# Board_Design.net
KiCad netlist of a schematic drawn in EAGLE
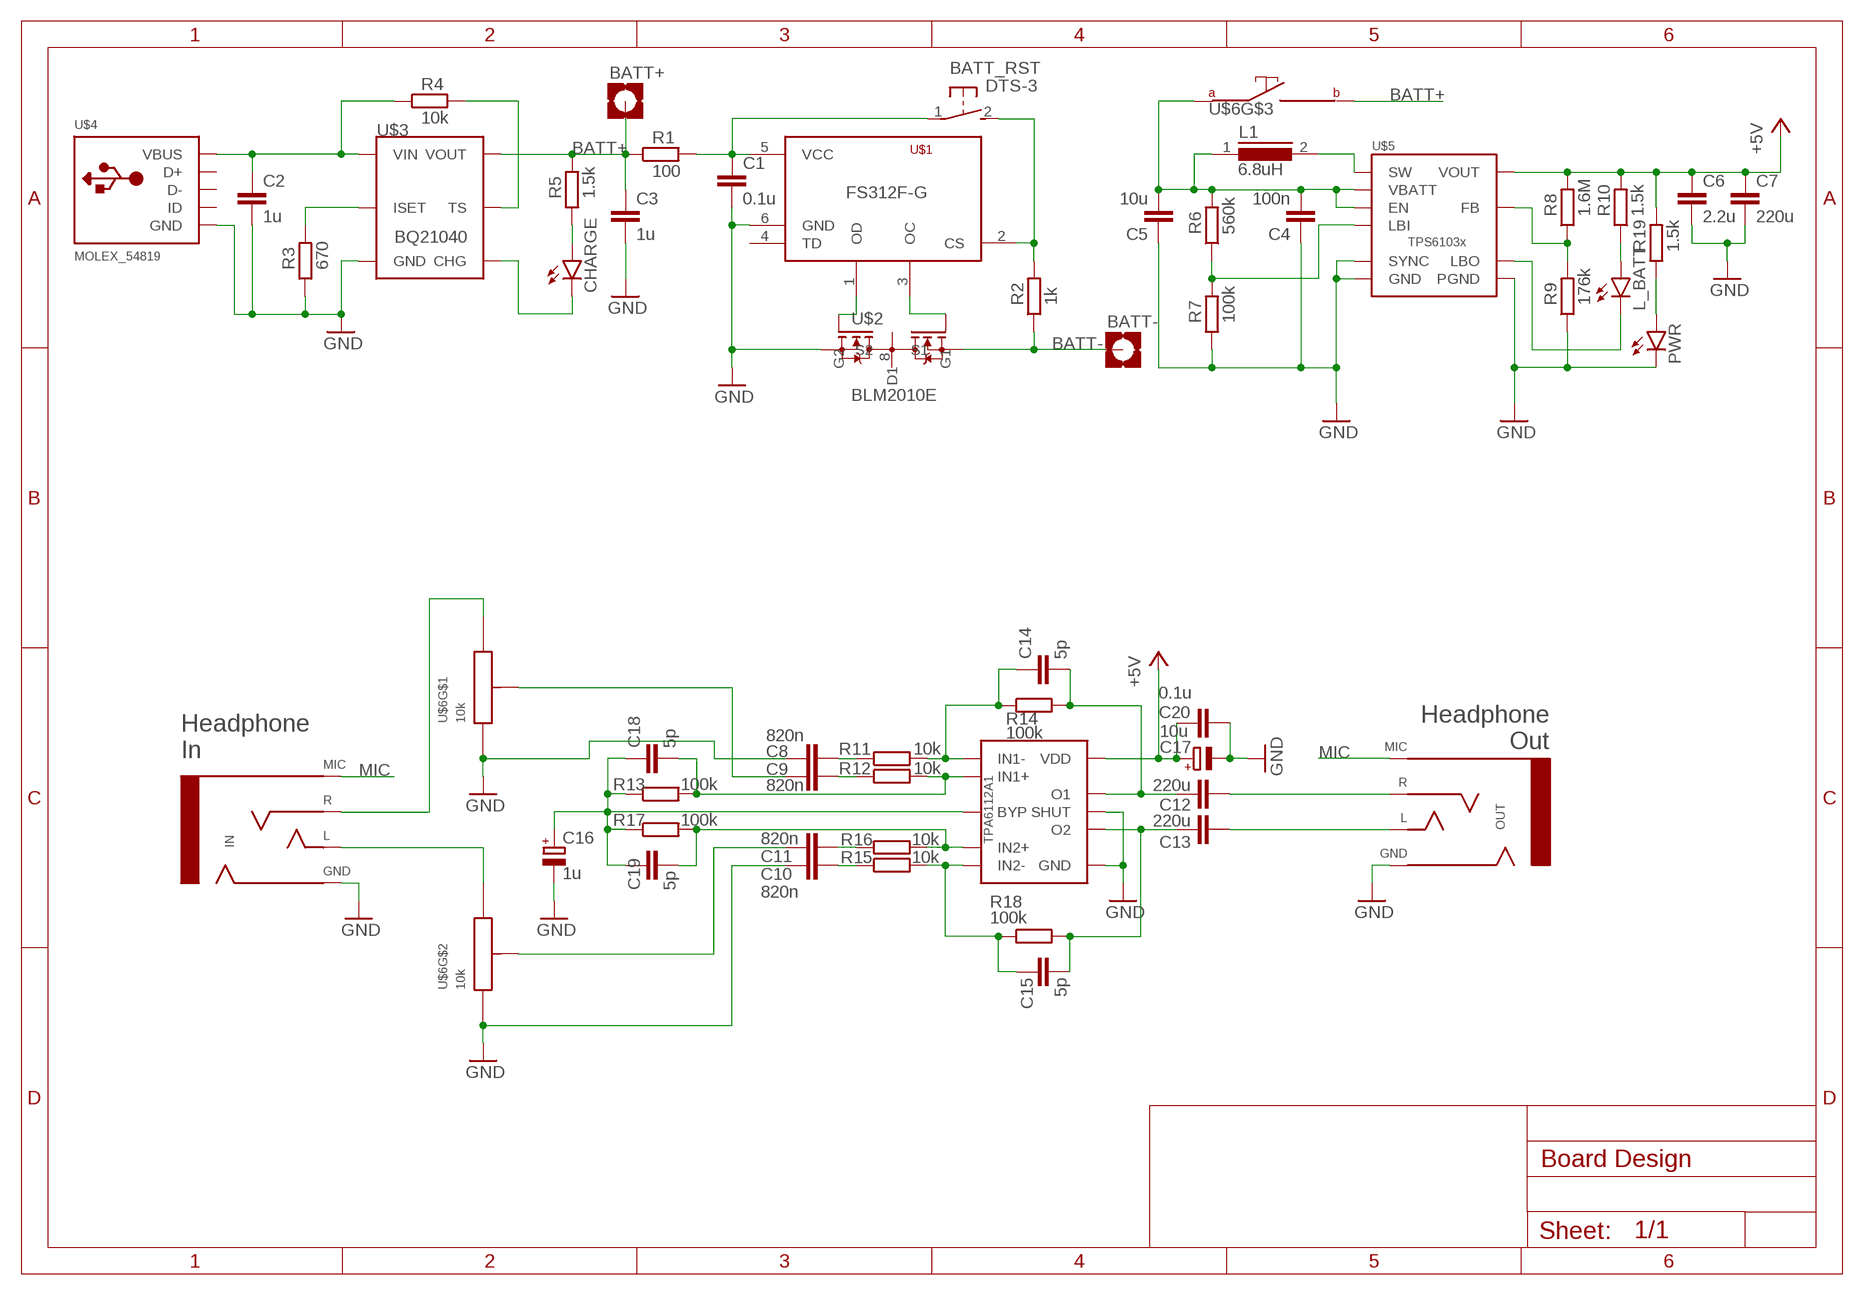
[diagram p0: schematic, sheet 1]

(export (version "E")
  (design (tool "Eeschema 10.0.6"))
  (components
    (comp (ref "BATT+")
      (value "MOUNT-PAD-SQUARE2.8")
      (footprint "eagle-import:2,8-PAD-SQUARE")
      (libsource (lib "eagle-import") (part "MOUNT-PAD-SQUARE2.8"))
    )
    (comp (ref "BATT-")
      (value "MOUNT-PAD-SQUARE2.8")
      (footprint "eagle-import:2,8-PAD-SQUARE")
      (libsource (lib "eagle-import") (part "MOUNT-PAD-SQUARE2.8"))
    )
    (comp (ref "BATT_RST")
      (value "DTS-3")
      (footprint "eagle-import:DTS-3")
      (libsource (lib "eagle-import") (part "DTS-3"))
    )
    (comp (ref "C1")
      (value "0.1u")
      (footprint "eagle-import:C1206")
      (libsource (lib "eagle-import") (part "C-EUC1206"))
    )
    (comp (ref "C2")
      (value "1u")
      (footprint "eagle-import:C1206")
      (libsource (lib "eagle-import") (part "C-EUC1206"))
    )
    (comp (ref "C3")
      (value "1u")
      (footprint "eagle-import:C1206")
      (libsource (lib "eagle-import") (part "C-EUC1206"))
    )
    (comp (ref "C4")
      (value "100n")
      (footprint "eagle-import:C1206")
      (libsource (lib "eagle-import") (part "C-EUC1206"))
    )
    (comp (ref "C5")
      (value "10u")
      (footprint "eagle-import:C1206")
      (libsource (lib "eagle-import") (part "C-EUC1206"))
    )
    (comp (ref "C6")
      (value "2.2u")
      (footprint "eagle-import:C1206")
      (libsource (lib "eagle-import") (part "C-EUC1206"))
    )
    (comp (ref "C7")
      (value "220u")
      (footprint "eagle-import:C1206")
      (libsource (lib "eagle-import") (part "C-EUC1206"))
    )
    (comp (ref "C8")
      (value "820n")
      (footprint "eagle-import:C1812")
      (libsource (lib "eagle-import") (part "C-EUC1812"))
    )
    (comp (ref "C9")
      (value "820n")
      (footprint "eagle-import:C1812")
      (libsource (lib "eagle-import") (part "C-EUC1812"))
    )
    (comp (ref "C10")
      (value "820n")
      (footprint "eagle-import:C1812")
      (libsource (lib "eagle-import") (part "C-EUC1812"))
    )
    (comp (ref "C11")
      (value "820n")
      (footprint "eagle-import:C1812")
      (libsource (lib "eagle-import") (part "C-EUC1812"))
    )
    (comp (ref "C12")
      (value "220u")
      (footprint "eagle-import:C1210")
      (libsource (lib "eagle-import") (part "C-EUC1210"))
    )
    (comp (ref "C13")
      (value "220u")
      (footprint "eagle-import:C1210")
      (libsource (lib "eagle-import") (part "C-EUC1210"))
    )
    (comp (ref "C14")
      (value "5p")
      (footprint "eagle-import:C1206")
      (libsource (lib "eagle-import") (part "C-EUC1206"))
    )
    (comp (ref "C15")
      (value "5p")
      (footprint "eagle-import:C1206")
      (libsource (lib "eagle-import") (part "C-EUC1206"))
    )
    (comp (ref "C16")
      (value "1u")
      (footprint "eagle-import:PANASONIC_B")
      (libsource (lib "eagle-import") (part "CPOL-EUB"))
    )
    (comp (ref "C17")
      (value "10u")
      (footprint "eagle-import:PANASONIC_B")
      (libsource (lib "eagle-import") (part "CPOL-EUB"))
    )
    (comp (ref "C18")
      (value "5p")
      (footprint "eagle-import:C1206")
      (libsource (lib "eagle-import") (part "C-EUC1206"))
    )
    (comp (ref "C19")
      (value "5p")
      (footprint "eagle-import:C1206")
      (libsource (lib "eagle-import") (part "C-EUC1206"))
    )
    (comp (ref "C20")
      (value "0.1u")
      (footprint "eagle-import:C1206")
      (libsource (lib "eagle-import") (part "C-EUC1206"))
    )
    (comp (ref "CHARGE")
      (value "LEDSMT1206")
      (footprint "eagle-import:1206")
      (libsource (lib "eagle-import") (part "LEDSMT1206"))
    )
    (comp (ref "IN")
      (value "PJ-35372")
      (footprint "eagle-import:PJ-35372")
      (libsource (lib "eagle-import") (part "PJ-35372"))
    )
    (comp (ref "L1")
      (value "6.8uH")
      (footprint "eagle-import:DR127")
      (libsource (lib "eagle-import") (part "DR127"))
    )
    (comp (ref "L_BATT")
      (value "LEDSMT1206")
      (footprint "eagle-import:1206")
      (libsource (lib "eagle-import") (part "LEDSMT1206"))
    )
    (comp (ref "OUT")
      (value "PJ-35372")
      (footprint "eagle-import:PJ-35372")
      (libsource (lib "eagle-import") (part "PJ-35372"))
    )
    (comp (ref "PWR")
      (value "LEDSMT1206")
      (footprint "eagle-import:1206")
      (libsource (lib "eagle-import") (part "LEDSMT1206"))
    )
    (comp (ref "R1")
      (value "100")
      (footprint "eagle-import:M1206")
      (libsource (lib "eagle-import") (part "R-EU_M1206"))
    )
    (comp (ref "R2")
      (value "1k")
      (footprint "eagle-import:M1206")
      (libsource (lib "eagle-import") (part "R-EU_M1206"))
    )
    (comp (ref "R3")
      (value "670")
      (footprint "eagle-import:M1206")
      (libsource (lib "eagle-import") (part "R-EU_M1206"))
    )
    (comp (ref "R4")
      (value "10k")
      (footprint "eagle-import:M1206")
      (libsource (lib "eagle-import") (part "R-EU_M1206"))
    )
    (comp (ref "R5")
      (value "1.5k")
      (footprint "eagle-import:M1206")
      (libsource (lib "eagle-import") (part "R-EU_M1206"))
    )
    (comp (ref "R6")
      (value "560k")
      (footprint "eagle-import:M1206")
      (libsource (lib "eagle-import") (part "R-EU_M1206"))
    )
    (comp (ref "R7")
      (value "100k")
      (footprint "eagle-import:M1206")
      (libsource (lib "eagle-import") (part "R-EU_M1206"))
    )
    (comp (ref "R8")
      (value "1.6M")
      (footprint "eagle-import:M1206")
      (libsource (lib "eagle-import") (part "R-EU_M1206"))
    )
    (comp (ref "R9")
      (value "176k")
      (footprint "eagle-import:M1206")
      (libsource (lib "eagle-import") (part "R-EU_M1206"))
    )
    (comp (ref "R10")
      (value "1.5k")
      (footprint "eagle-import:M1206")
      (libsource (lib "eagle-import") (part "R-EU_M1206"))
    )
    (comp (ref "R11")
      (value "10k")
      (footprint "eagle-import:0204V")
      (libsource (lib "eagle-import") (part "R-EU_0204/2V"))
    )
    (comp (ref "R12")
      (value "10k")
      (footprint "eagle-import:0204V")
      (libsource (lib "eagle-import") (part "R-EU_0204/2V"))
    )
    (comp (ref "R13")
      (value "100k")
      (footprint "eagle-import:0204V")
      (libsource (lib "eagle-import") (part "R-EU_0204/2V"))
    )
    (comp (ref "R14")
      (value "100k")
      (footprint "eagle-import:0204V")
      (libsource (lib "eagle-import") (part "R-EU_0204/2V"))
    )
    (comp (ref "R15")
      (value "10k")
      (footprint "eagle-import:0204V")
      (libsource (lib "eagle-import") (part "R-EU_0204/2V"))
    )
    (comp (ref "R16")
      (value "10k")
      (footprint "eagle-import:0204V")
      (libsource (lib "eagle-import") (part "R-EU_0204/2V"))
    )
    (comp (ref "R17")
      (value "100k")
      (footprint "eagle-import:0204V")
      (libsource (lib "eagle-import") (part "R-EU_0204/2V"))
    )
    (comp (ref "R18")
      (value "100k")
      (footprint "eagle-import:0204V")
      (libsource (lib "eagle-import") (part "R-EU_0204/2V"))
    )
    (comp (ref "R19")
      (value "1.5k")
      (footprint "eagle-import:M1206")
      (libsource (lib "eagle-import") (part "R-EU_M1206"))
    )
    (comp (ref "TPA6112A1")
      (value "TPA6112A2")
      (footprint "eagle-import:MSOP-10")
      (libsource (lib "eagle-import") (part "TPA6112A2"))
    )
    (comp (ref "U$1")
      (value "FS312F-G")
      (footprint "eagle-import:SOT23-6")
      (libsource (lib "eagle-import") (part "FS312F-G"))
    )
    (comp (ref "U$2")
      (value "BLM2010E")
      (footprint "eagle-import:TSSOP8")
      (libsource (lib "eagle-import") (part "BLM2010E"))
    )
    (comp (ref "U$3")
      (value "BQ21040M")
      (footprint "eagle-import:SOT23-6")
      (fields (field (name "SPICEPREFIX") "X"))
      (libsource (lib "eagle-import") (part "BQ21040M"))
    )
    (comp (ref "U$4")
      (value "MOLEX_54819")
      (footprint "eagle-import:MOLEX_54819")
      (libsource (lib "eagle-import") (part "MOLEX_54819"))
    )
    (comp (ref "U$5")
      (value "TPS61032")
      (footprint "eagle-import:TSSOP16L")
      (fields (field (name "SPICEPREFIX") "X"))
      (libsource (lib "eagle-import") (part "TPS61032"))
    )
    (comp (ref "U$6")
      (value "10k")
      (footprint "eagle-import:RK097-DUAL-ELEMENT-W_SWITCH")
      (libsource (lib "eagle-import") (part "RK097-DUAL-W/SWITCH"))
    )
  )
  (nets
    (net (code "1") (name "+5V") (class "Default")
      (node (ref "C17") (pin "+") (pinfunction "+_+") (pintype "passive"))
      (node (ref "C20") (pin "1") (pinfunction "1_1") (pintype "passive"))
      (node (ref "C6") (pin "1") (pinfunction "1_1") (pintype "passive"))
      (node (ref "C7") (pin "1") (pinfunction "1_1") (pintype "passive"))
      (node (ref "R10") (pin "2") (pinfunction "2_2") (pintype "passive"))
      (node (ref "R19") (pin "2") (pinfunction "2_2") (pintype "passive"))
      (node (ref "R8") (pin "2") (pinfunction "2_2") (pintype "passive"))
      (node (ref "TPA6112A1") (pin "10") (pinfunction "VDD_10") (pintype "bidirectional"))
      (node (ref "U$5") (pin "13") (pinfunction "VOUT_13") (pintype "power_in"))
      (node (ref "U$5") (pin "14") (pinfunction "VOUT_14") (pintype "power_in"))
      (node (ref "U$5") (pin "15") (pinfunction "VOUT_15") (pintype "power_in"))
    )
    (net (code "2") (name "/BATT+") (class "Default")
      (node (ref "BATT+") (pin "B2,8") (pinfunction "MOUNT_B2,8") (pintype "passive"))
      (node (ref "C3") (pin "1") (pinfunction "1_1") (pintype "passive"))
      (node (ref "R1") (pin "1") (pinfunction "1_1") (pintype "passive"))
      (node (ref "R5") (pin "2") (pinfunction "2_2") (pintype "passive"))
      (node (ref "U$3") (pin "2") (pinfunction "VOUT_2") (pintype "power_in"))
      (node (ref "U$6") (pin "S2") (pinfunction "P$2_S2") (pintype "passive"))
    )
    (net (code "3") (name "/BATT-") (class "Default")
      (node (ref "BATT-") (pin "B2,8") (pinfunction "MOUNT_B2,8") (pintype "passive"))
      (node (ref "R2") (pin "1") (pinfunction "1_1") (pintype "passive"))
      (node (ref "U$2") (pin "2") (pinfunction "S1_2") (pintype "passive"))
      (node (ref "U$2") (pin "3") (pinfunction "S1_3") (pintype "passive"))
    )
    (net (code "4") (name "/MIC") (class "Default")
      (node (ref "IN") (pin "1") (pinfunction "S_1") (pintype "bidirectional"))
      (node (ref "IN") (pin "5") (pinfunction "S_5") (pintype "bidirectional"))
      (node (ref "OUT") (pin "1") (pinfunction "S_1") (pintype "bidirectional"))
      (node (ref "OUT") (pin "5") (pinfunction "S_5") (pintype "bidirectional"))
    )
    (net (code "5") (name "GND") (class "Default")
      (node (ref "C1") (pin "2") (pinfunction "2_2") (pintype "passive"))
      (node (ref "C10") (pin "1") (pinfunction "1_1") (pintype "passive"))
      (node (ref "C16") (pin "-") (pinfunction "-_-") (pintype "passive"))
      (node (ref "C17") (pin "-") (pinfunction "-_-") (pintype "passive"))
      (node (ref "C2") (pin "2") (pinfunction "2_2") (pintype "passive"))
      (node (ref "C20") (pin "2") (pinfunction "2_2") (pintype "passive"))
      (node (ref "C3") (pin "2") (pinfunction "2_2") (pintype "passive"))
      (node (ref "C4") (pin "1") (pinfunction "1_1") (pintype "passive"))
      (node (ref "C5") (pin "1") (pinfunction "1_1") (pintype "passive"))
      (node (ref "C6") (pin "2") (pinfunction "2_2") (pintype "passive"))
      (node (ref "C7") (pin "2") (pinfunction "2_2") (pintype "passive"))
      (node (ref "C8") (pin "1") (pinfunction "1_1") (pintype "passive"))
      (node (ref "IN") (pin "2") (pinfunction "R2_2") (pintype "bidirectional"))
      (node (ref "IN") (pin "6") (pinfunction "R2_6") (pintype "bidirectional"))
      (node (ref "OUT") (pin "2") (pinfunction "R2_2") (pintype "bidirectional"))
      (node (ref "OUT") (pin "6") (pinfunction "R2_6") (pintype "bidirectional"))
      (node (ref "PWR") (pin "C") (pinfunction "C_C") (pintype "passive"))
      (node (ref "R3") (pin "1") (pinfunction "1_1") (pintype "passive"))
      (node (ref "R7") (pin "1") (pinfunction "1_1") (pintype "passive"))
      (node (ref "R9") (pin "1") (pinfunction "1_1") (pintype "passive"))
      (node (ref "TPA6112A1") (pin "5") (pinfunction "GND_5") (pintype "bidirectional"))
      (node (ref "TPA6112A1") (pin "6") (pinfunction "SHUT_6") (pintype "bidirectional"))
      (node (ref "U$1") (pin "6") (pinfunction "GND_6") (pintype "bidirectional"))
      (node (ref "U$2") (pin "6") (pinfunction "S2_6") (pintype "passive"))
      (node (ref "U$2") (pin "7") (pinfunction "S2_7") (pintype "passive"))
      (node (ref "U$3") (pin "5") (pinfunction "GND_5") (pintype "power_in"))
      (node (ref "U$4") (pin "GND") (pinfunction "GND_GND") (pintype "power_in"))
      (node (ref "U$5") (pin "11") (pinfunction "GND_11") (pintype "power_in"))
      (node (ref "U$5") (pin "3") (pinfunction "PGND_3") (pintype "power_in"))
      (node (ref "U$5") (pin "4") (pinfunction "PGND_4") (pintype "power_in"))
      (node (ref "U$5") (pin "5") (pinfunction "PGND_5") (pintype "power_in"))
      (node (ref "U$5") (pin "8") (pinfunction "SYNC_8") (pintype "bidirectional"))
      (node (ref "U$6") (pin "1-1") (pinfunction "1_1-1") (pintype "passive"))
      (node (ref "U$6") (pin "2-1") (pinfunction "1_2-1") (pintype "passive"))
    )
    (net (code "6") (name "Net-(C8-Pad2)") (class "Default")
      (node (ref "C8") (pin "2") (pinfunction "2_2") (pintype "passive"))
      (node (ref "R11") (pin "1") (pinfunction "1_1") (pintype "passive"))
    )
    (net (code "7") (name "Net-(C9-Pad2)") (class "Default")
      (node (ref "C9") (pin "2") (pinfunction "2_2") (pintype "passive"))
      (node (ref "R12") (pin "1") (pinfunction "1_1") (pintype "passive"))
    )
    (net (code "8") (name "Net-(C10-Pad2)") (class "Default")
      (node (ref "C10") (pin "2") (pinfunction "2_2") (pintype "passive"))
      (node (ref "R15") (pin "1") (pinfunction "1_1") (pintype "passive"))
    )
    (net (code "9") (name "Net-(C11-Pad2)") (class "Default")
      (node (ref "C11") (pin "2") (pinfunction "2_2") (pintype "passive"))
      (node (ref "R16") (pin "1") (pinfunction "1_1") (pintype "passive"))
    )
    (net (code "10") (name "Net-(C12-Pad2)") (class "Default")
      (node (ref "C12") (pin "2") (pinfunction "2_2") (pintype "passive"))
      (node (ref "OUT") (pin "3") (pinfunction "R1_3") (pintype "bidirectional"))
      (node (ref "OUT") (pin "7") (pinfunction "R1_7") (pintype "bidirectional"))
    )
    (net (code "11") (name "Net-(C13-Pad2)") (class "Default")
      (node (ref "C13") (pin "2") (pinfunction "2_2") (pintype "passive"))
      (node (ref "OUT") (pin "4") (pinfunction "T_4") (pintype "bidirectional"))
      (node (ref "OUT") (pin "8") (pinfunction "T_8") (pintype "bidirectional"))
    )
    (net (code "12") (name "Net-(CHARGE-PadA)") (class "Default")
      (node (ref "CHARGE") (pin "A") (pinfunction "A_A") (pintype "passive"))
      (node (ref "R5") (pin "1") (pinfunction "1_1") (pintype "passive"))
    )
    (net (code "13") (name "Net-(L1-Pad2)") (class "Default")
      (node (ref "L1") (pin "2") (pinfunction "2_2") (pintype "passive"))
      (node (ref "U$5") (pin "1") (pinfunction "SW_1") (pintype "bidirectional"))
      (node (ref "U$5") (pin "2") (pinfunction "SW_2") (pintype "bidirectional"))
    )
    (net (code "14") (name "Net-(L_BATT-PadA)") (class "Default")
      (node (ref "L_BATT") (pin "A") (pinfunction "A_A") (pintype "passive"))
      (node (ref "R10") (pin "1") (pinfunction "1_1") (pintype "passive"))
    )
    (net (code "15") (name "Net-(PWR-PadA)") (class "Default")
      (node (ref "PWR") (pin "A") (pinfunction "A_A") (pintype "passive"))
      (node (ref "R19") (pin "1") (pinfunction "1_1") (pintype "passive"))
    )
    (net (code "16") (name "Net-(TPA6112A1-BYP)") (class "Default")
      (node (ref "C16") (pin "+") (pinfunction "+_+") (pintype "passive"))
      (node (ref "C18") (pin "1") (pinfunction "1_1") (pintype "passive"))
      (node (ref "C19") (pin "1") (pinfunction "1_1") (pintype "passive"))
      (node (ref "R13") (pin "1") (pinfunction "1_1") (pintype "passive"))
      (node (ref "R17") (pin "1") (pinfunction "1_1") (pintype "passive"))
      (node (ref "TPA6112A1") (pin "4") (pinfunction "BYP_4") (pintype "bidirectional"))
    )
    (net (code "17") (name "Net-(TPA6112A1-IN1+)") (class "Default")
      (node (ref "C18") (pin "2") (pinfunction "2_2") (pintype "passive"))
      (node (ref "R12") (pin "2") (pinfunction "2_2") (pintype "passive"))
      (node (ref "R13") (pin "2") (pinfunction "2_2") (pintype "passive"))
      (node (ref "TPA6112A1") (pin "3") (pinfunction "IN1+_3") (pintype "bidirectional"))
    )
    (net (code "18") (name "Net-(TPA6112A1-IN1-)") (class "Default")
      (node (ref "C14") (pin "1") (pinfunction "1_1") (pintype "passive"))
      (node (ref "R11") (pin "2") (pinfunction "2_2") (pintype "passive"))
      (node (ref "R14") (pin "1") (pinfunction "1_1") (pintype "passive"))
      (node (ref "TPA6112A1") (pin "2") (pinfunction "IN1-_2") (pintype "bidirectional"))
    )
    (net (code "19") (name "Net-(TPA6112A1-IN2+)") (class "Default")
      (node (ref "C19") (pin "2") (pinfunction "2_2") (pintype "passive"))
      (node (ref "R16") (pin "2") (pinfunction "2_2") (pintype "passive"))
      (node (ref "R17") (pin "2") (pinfunction "2_2") (pintype "passive"))
      (node (ref "TPA6112A1") (pin "7") (pinfunction "IN2+_7") (pintype "bidirectional"))
    )
    (net (code "20") (name "Net-(TPA6112A1-IN2-)") (class "Default")
      (node (ref "C15") (pin "1") (pinfunction "1_1") (pintype "passive"))
      (node (ref "R15") (pin "2") (pinfunction "2_2") (pintype "passive"))
      (node (ref "R18") (pin "1") (pinfunction "1_1") (pintype "passive"))
      (node (ref "TPA6112A1") (pin "8") (pinfunction "IN2-_8") (pintype "bidirectional"))
    )
    (net (code "21") (name "Net-(TPA6112A1-O1)") (class "Default")
      (node (ref "C12") (pin "1") (pinfunction "1_1") (pintype "passive"))
      (node (ref "C14") (pin "2") (pinfunction "2_2") (pintype "passive"))
      (node (ref "R14") (pin "2") (pinfunction "2_2") (pintype "passive"))
      (node (ref "TPA6112A1") (pin "1") (pinfunction "O1_1") (pintype "bidirectional"))
    )
    (net (code "22") (name "Net-(TPA6112A1-O2)") (class "Default")
      (node (ref "C13") (pin "1") (pinfunction "1_1") (pintype "passive"))
      (node (ref "C15") (pin "2") (pinfunction "2_2") (pintype "passive"))
      (node (ref "R18") (pin "2") (pinfunction "2_2") (pintype "passive"))
      (node (ref "TPA6112A1") (pin "9") (pinfunction "O2_9") (pintype "bidirectional"))
    )
    (net (code "23") (name "Net-(U$1-CS)") (class "Default")
      (node (ref "BATT_RST") (pin "2") (pinfunction "2_2") (pintype "passive"))
      (node (ref "R2") (pin "2") (pinfunction "2_2") (pintype "passive"))
      (node (ref "U$1") (pin "2") (pinfunction "CS_2") (pintype "bidirectional"))
    )
    (net (code "24") (name "Net-(U$1-OC)") (class "Default")
      (node (ref "U$1") (pin "3") (pinfunction "OC_3") (pintype "bidirectional"))
      (node (ref "U$2") (pin "4") (pinfunction "G1_4") (pintype "passive"))
    )
    (net (code "25") (name "Net-(U$1-OD)") (class "Default")
      (node (ref "U$1") (pin "1") (pinfunction "OD_1") (pintype "bidirectional"))
      (node (ref "U$2") (pin "5") (pinfunction "G2_5") (pintype "passive"))
    )
    (net (code "26") (name "Net-(U$1-VCC)") (class "Default")
      (node (ref "BATT_RST") (pin "1") (pinfunction "1_1") (pintype "passive"))
      (node (ref "C1") (pin "1") (pinfunction "1_1") (pintype "passive"))
      (node (ref "R1") (pin "2") (pinfunction "2_2") (pintype "passive"))
      (node (ref "U$1") (pin "5") (pinfunction "VCC_5") (pintype "bidirectional"))
    )
    (net (code "27") (name "Net-(U$3-CHG)") (class "Default")
      (node (ref "CHARGE") (pin "C") (pinfunction "C_C") (pintype "passive"))
      (node (ref "U$3") (pin "3") (pinfunction "CHG_3") (pintype "output"))
    )
    (net (code "28") (name "Net-(U$3-ISET)") (class "Default")
      (node (ref "R3") (pin "2") (pinfunction "2_2") (pintype "passive"))
      (node (ref "U$3") (pin "6") (pinfunction "ISET_6") (pintype "input"))
    )
    (net (code "29") (name "Net-(U$3-TS)") (class "Default")
      (node (ref "R4") (pin "2") (pinfunction "2_2") (pintype "passive"))
      (node (ref "U$3") (pin "1") (pinfunction "TS_1") (pintype "input"))
    )
    (net (code "30") (name "Net-(U$3-VIN)") (class "Default")
      (node (ref "C2") (pin "1") (pinfunction "1_1") (pintype "passive"))
      (node (ref "R4") (pin "1") (pinfunction "1_1") (pintype "passive"))
      (node (ref "U$3") (pin "4") (pinfunction "VIN_4") (pintype "power_in"))
      (node (ref "U$4") (pin "VBUS") (pinfunction "VBUS_VBUS") (pintype "power_in"))
    )
    (net (code "31") (name "Net-(U$5-EN)") (class "Default")
      (node (ref "C4") (pin "2") (pinfunction "2_2") (pintype "passive"))
      (node (ref "C5") (pin "2") (pinfunction "2_2") (pintype "passive"))
      (node (ref "L1") (pin "1") (pinfunction "1_1") (pintype "passive"))
      (node (ref "R6") (pin "2") (pinfunction "2_2") (pintype "passive"))
      (node (ref "U$5") (pin "6") (pinfunction "VBATT_6") (pintype "power_in"))
      (node (ref "U$5") (pin "9") (pinfunction "EN_9") (pintype "bidirectional"))
      (node (ref "U$6") (pin "S1") (pinfunction "P$1_S1") (pintype "passive"))
    )
    (net (code "32") (name "Net-(U$5-FB)") (class "Default")
      (node (ref "R8") (pin "1") (pinfunction "1_1") (pintype "passive"))
      (node (ref "R9") (pin "2") (pinfunction "2_2") (pintype "passive"))
      (node (ref "U$5") (pin "12") (pinfunction "FB_12") (pintype "bidirectional"))
    )
    (net (code "33") (name "Net-(U$5-LBI)") (class "Default")
      (node (ref "R6") (pin "1") (pinfunction "1_1") (pintype "passive"))
      (node (ref "R7") (pin "2") (pinfunction "2_2") (pintype "passive"))
      (node (ref "U$5") (pin "7") (pinfunction "LBI_7") (pintype "bidirectional"))
    )
    (net (code "34") (name "Net-(U$5-LBO)") (class "Default")
      (node (ref "L_BATT") (pin "C") (pinfunction "C_C") (pintype "passive"))
      (node (ref "U$5") (pin "10") (pinfunction "LBO_10") (pintype "bidirectional"))
    )
    (net (code "35") (name "Net-(U$6A-2)") (class "Default")
      (node (ref "IN") (pin "3") (pinfunction "R1_3") (pintype "bidirectional"))
      (node (ref "IN") (pin "7") (pinfunction "R1_7") (pintype "bidirectional"))
      (node (ref "U$6") (pin "1-2") (pinfunction "2_1-2") (pintype "passive"))
    )
    (net (code "36") (name "Net-(U$6A-3)") (class "Default")
      (node (ref "C9") (pin "1") (pinfunction "1_1") (pintype "passive"))
      (node (ref "U$6") (pin "1-3") (pinfunction "3_1-3") (pintype "passive"))
    )
    (net (code "37") (name "Net-(U$6B-2)") (class "Default")
      (node (ref "IN") (pin "4") (pinfunction "T_4") (pintype "bidirectional"))
      (node (ref "IN") (pin "8") (pinfunction "T_8") (pintype "bidirectional"))
      (node (ref "U$6") (pin "2-2") (pinfunction "2_2-2") (pintype "passive"))
    )
    (net (code "38") (name "Net-(U$6B-3)") (class "Default")
      (node (ref "C11") (pin "1") (pinfunction "1_1") (pintype "passive"))
      (node (ref "U$6") (pin "2-3") (pinfunction "3_2-3") (pintype "passive"))
    )
    (net (code "39") (name "unconnected-(U$1-TD-Pad4)") (class "Default")
      (node (ref "U$1") (pin "4") (pinfunction "TD_4") (pintype "bidirectional"))
    )
    (net (code "40") (name "unconnected-(U$2-D1-Pad1)") (class "Default")
      (node (ref "U$2") (pin "1") (pinfunction "D1_1") (pintype "passive"))
    )
    (net (code "41") (name "unconnected-(U$2-D2-Pad8)") (class "Default")
      (node (ref "U$2") (pin "8") (pinfunction "D2_8") (pintype "passive"))
    )
    (net (code "42") (name "unconnected-(U$4-PadD+)") (class "Default")
      (node (ref "U$4") (pin "D+") (pinfunction "D+_D+") (pintype "bidirectional"))
    )
    (net (code "43") (name "unconnected-(U$4-PadD-)") (class "Default")
      (node (ref "U$4") (pin "D-") (pinfunction "D-_D-") (pintype "bidirectional"))
    )
    (net (code "44") (name "unconnected-(U$4-PadID)") (class "Default")
      (node (ref "U$4") (pin "ID") (pinfunction "ID_ID") (pintype "bidirectional"))
    )
  )
)
